# MicroController_RGB_LED.net
KiCad netlist of a schematic drawn in Altium Designer
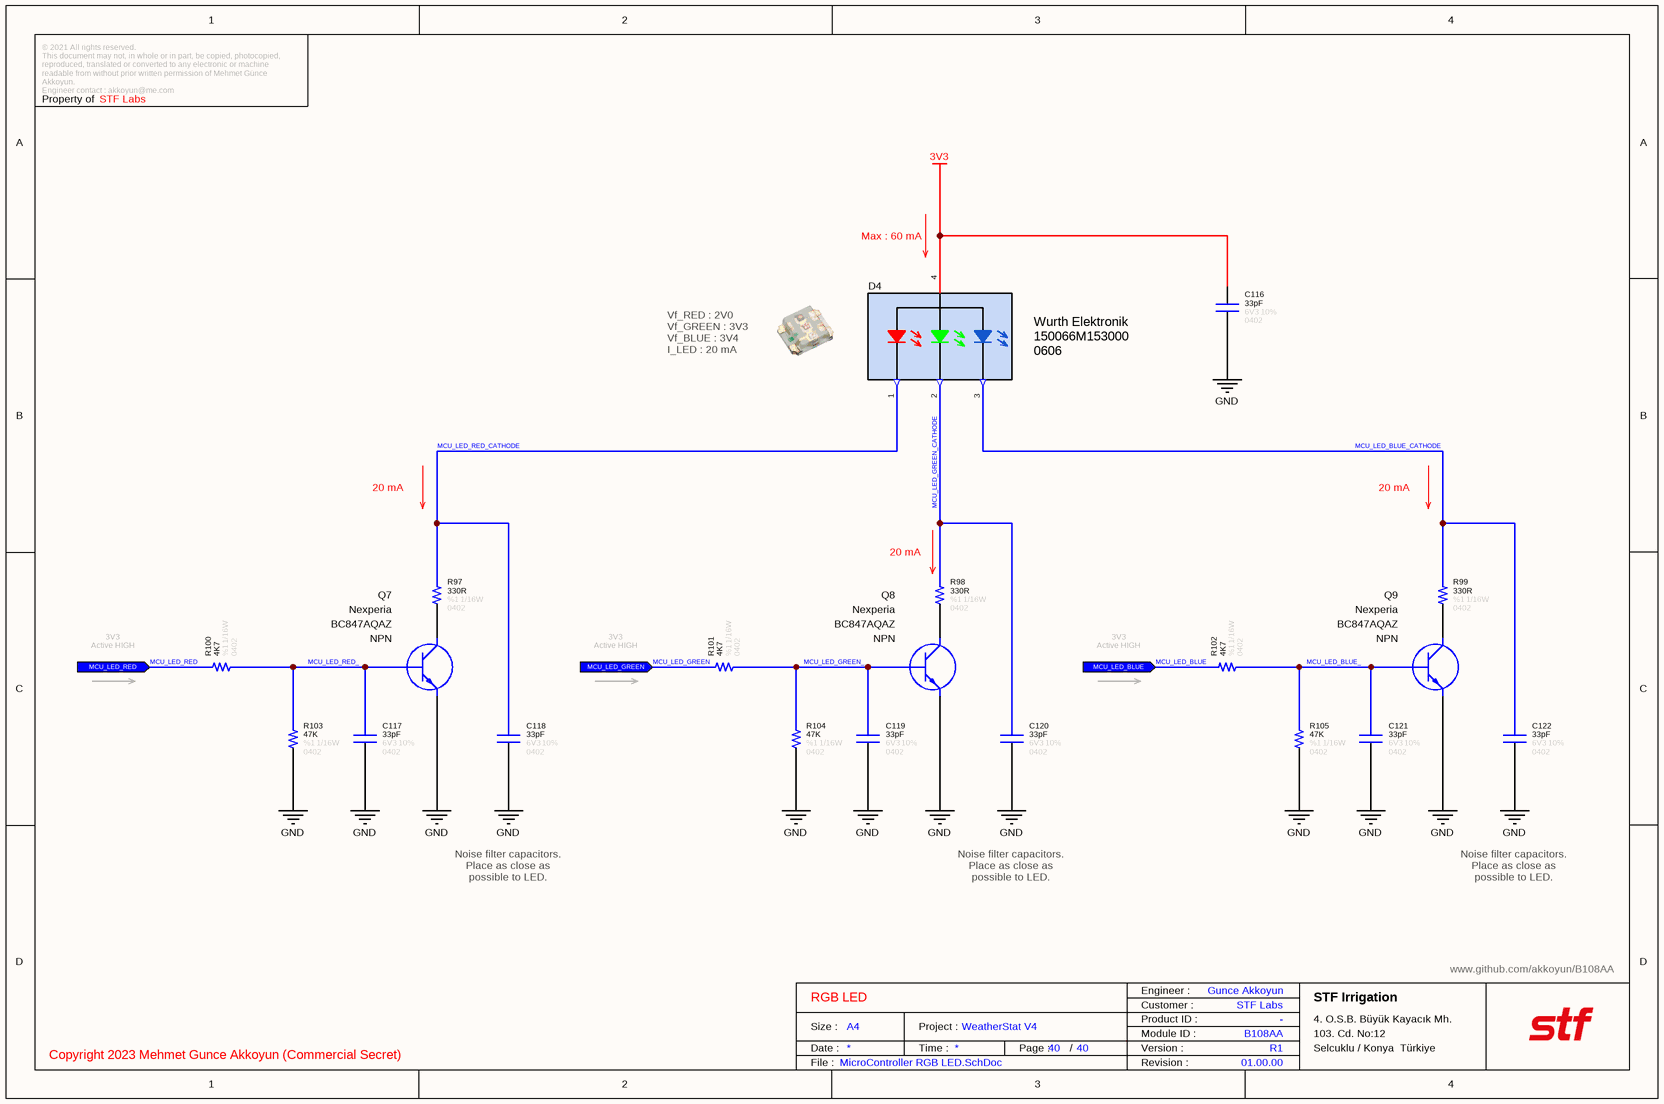
[diagram p0: MicroController RGB LED.SchDoc]

(export (version "E")
  (design (tool "Eeschema 10.0.6"))
  (components
    (comp (ref "C116")
      (value "33pF")
      (footprint "CAPACITOR_0402")
      (description "Capacitor - 33pF [0402] (Ceramic)")
      (fields
        (field (name "MANUFACTURER PART NUMBER") "C0402C330J9RACAUTO")
        (field (name "TOLERANCE") "10%")
        (field (name "CASE") "0402")
        (field (name "VOLTAGE") "6V3")
      )
      (libsource (lib "Akkoyun") (part "Capacitor - 33pF [0402-6V3]"))
    )
    (comp (ref "C117")
      (value "33pF")
      (footprint "CAPACITOR_0402")
      (description "Capacitor - 33pF [0402] (Ceramic)")
      (fields
        (field (name "MANUFACTURER PART NUMBER") "C0402C330J9RACAUTO")
        (field (name "TOLERANCE") "10%")
        (field (name "CASE") "0402")
        (field (name "VOLTAGE") "6V3")
      )
      (libsource (lib "Akkoyun") (part "Capacitor - 33pF [0402-6V3]"))
    )
    (comp (ref "C118")
      (value "33pF")
      (footprint "CAPACITOR_0402")
      (description "Capacitor - 33pF [0402] (Ceramic)")
      (fields
        (field (name "MANUFACTURER PART NUMBER") "C0402C330J9RACAUTO")
        (field (name "TOLERANCE") "10%")
        (field (name "CASE") "0402")
        (field (name "VOLTAGE") "6V3")
      )
      (libsource (lib "Akkoyun") (part "Capacitor - 33pF [0402-6V3]"))
    )
    (comp (ref "C119")
      (value "33pF")
      (footprint "CAPACITOR_0402")
      (description "Capacitor - 33pF [0402] (Ceramic)")
      (fields
        (field (name "MANUFACTURER PART NUMBER") "C0402C330J9RACAUTO")
        (field (name "TOLERANCE") "10%")
        (field (name "CASE") "0402")
        (field (name "VOLTAGE") "6V3")
      )
      (libsource (lib "Akkoyun") (part "Capacitor - 33pF [0402-6V3]"))
    )
    (comp (ref "C120")
      (value "33pF")
      (footprint "CAPACITOR_0402")
      (description "Capacitor - 33pF [0402] (Ceramic)")
      (fields
        (field (name "MANUFACTURER PART NUMBER") "C0402C330J9RACAUTO")
        (field (name "TOLERANCE") "10%")
        (field (name "CASE") "0402")
        (field (name "VOLTAGE") "6V3")
      )
      (libsource (lib "Akkoyun") (part "Capacitor - 33pF [0402-6V3]"))
    )
    (comp (ref "C121")
      (value "33pF")
      (footprint "CAPACITOR_0402")
      (description "Capacitor - 33pF [0402] (Ceramic)")
      (fields
        (field (name "MANUFACTURER PART NUMBER") "C0402C330J9RACAUTO")
        (field (name "TOLERANCE") "10%")
        (field (name "CASE") "0402")
        (field (name "VOLTAGE") "6V3")
      )
      (libsource (lib "Akkoyun") (part "Capacitor - 33pF [0402-6V3]"))
    )
    (comp (ref "C122")
      (value "33pF")
      (footprint "CAPACITOR_0402")
      (description "Capacitor - 33pF [0402] (Ceramic)")
      (fields
        (field (name "MANUFACTURER PART NUMBER") "C0402C330J9RACAUTO")
        (field (name "TOLERANCE") "10%")
        (field (name "CASE") "0402")
        (field (name "VOLTAGE") "6V3")
      )
      (libsource (lib "Akkoyun") (part "Capacitor - 33pF [0402-6V3]"))
    )
    (comp (ref "D4")
      (value "150066M153000")
      (footprint "Wurth_0606")
      (description "LED RGB DIFFUSED SMD")
      (fields
        (field (name "MANUFACTURER NAME") "Wurth Elektronik")
        (field (name "MANUFACTURER PART NUMBER") "150066M153000")
        (field (name "CASE") "0606")
      )
      (libsource (lib "Akkoyun") (part "Diode - LED-RGB"))
    )
    (comp (ref "Q7")
      (value "BC847AQAZ")
      (footprint "SOT1215")
      (description "Bipolar NPN Transistors")
      (fields
        (field (name "MANUFACTURER NAME") "Nexperia")
        (field (name "MANUFACTURER PART NUMBER") "BC847AQAZ")
        (field (name "POLARITY") "NPN")
      )
      (libsource (lib "Akkoyun") (part "Transistor - BC847"))
    )
    (comp (ref "Q8")
      (value "BC847AQAZ")
      (footprint "SOT1215")
      (description "Bipolar NPN Transistors")
      (fields
        (field (name "MANUFACTURER NAME") "Nexperia")
        (field (name "MANUFACTURER PART NUMBER") "BC847AQAZ")
        (field (name "POLARITY") "NPN")
      )
      (libsource (lib "Akkoyun") (part "Transistor - BC847"))
    )
    (comp (ref "Q9")
      (value "BC847AQAZ")
      (footprint "SOT1215")
      (description "Bipolar NPN Transistors")
      (fields
        (field (name "MANUFACTURER NAME") "Nexperia")
        (field (name "MANUFACTURER PART NUMBER") "BC847AQAZ")
        (field (name "POLARITY") "NPN")
      )
      (libsource (lib "Akkoyun") (part "Transistor - BC847"))
    )
    (comp (ref "R97")
      (value "330R")
      (footprint "RESISTOR_0402")
      (description "Thick Film Resistors - SMD 1/16 W 330 Ohm 1%")
      (fields
        (field (name "MANUFACTURER PART NUMBER") "CRCW0402330RFKED")
        (field (name "CASE") "0402")
        (field (name "TOLERANCE") "%1")
        (field (name "POWER") "1/16W")
        (field (name "Comment") "330R - 0402 - %1 - 1/16W")
      )
      (libsource (lib "Akkoyun") (part "Resistor - 330R [0402]"))
    )
    (comp (ref "R98")
      (value "330R")
      (footprint "RESISTOR_0402")
      (description "Thick Film Resistors - SMD 1/16 W 330 Ohm 1%")
      (fields
        (field (name "MANUFACTURER PART NUMBER") "CRCW0402330RFKED")
        (field (name "CASE") "0402")
        (field (name "TOLERANCE") "%1")
        (field (name "POWER") "1/16W")
        (field (name "Comment") "330R - 0402 - %1 - 1/16W")
      )
      (libsource (lib "Akkoyun") (part "Resistor - 330R [0402]"))
    )
    (comp (ref "R99")
      (value "330R")
      (footprint "RESISTOR_0402")
      (description "Thick Film Resistors - SMD 1/16 W 330 Ohm 1%")
      (fields
        (field (name "MANUFACTURER PART NUMBER") "CRCW0402330RFKED")
        (field (name "CASE") "0402")
        (field (name "TOLERANCE") "%1")
        (field (name "POWER") "1/16W")
        (field (name "Comment") "330R - 0402 - %1 - 1/16W")
      )
      (libsource (lib "Akkoyun") (part "Resistor - 330R [0402]"))
    )
    (comp (ref "R100")
      (value "4K7")
      (footprint "RESISTOR_0402")
      (description "Thick Film Resistors - SMD 1/16 W 4.7 KOhm 1%")
      (fields
        (field (name "MANUFACTURER PART NUMBER") "CRCW04024K70FKED")
        (field (name "TOLERANCE") "%1")
        (field (name "CASE") "0402")
        (field (name "POWER") "1/16W")
        (field (name "Comment") "4K7 - 0402 - %1 - 1/16W")
      )
      (libsource (lib "Akkoyun") (part "Resistor - 4K7 [0402]"))
    )
    (comp (ref "R101")
      (value "4K7")
      (footprint "RESISTOR_0402")
      (description "Thick Film Resistors - SMD 1/16 W 4.7 KOhm 1%")
      (fields
        (field (name "MANUFACTURER PART NUMBER") "CRCW04024K70FKED")
        (field (name "TOLERANCE") "%1")
        (field (name "CASE") "0402")
        (field (name "POWER") "1/16W")
        (field (name "Comment") "4K7 - 0402 - %1 - 1/16W")
      )
      (libsource (lib "Akkoyun") (part "Resistor - 4K7 [0402]"))
    )
    (comp (ref "R102")
      (value "4K7")
      (footprint "RESISTOR_0402")
      (description "Thick Film Resistors - SMD 1/16 W 4.7 KOhm 1%")
      (fields
        (field (name "MANUFACTURER PART NUMBER") "CRCW04024K70FKED")
        (field (name "TOLERANCE") "%1")
        (field (name "CASE") "0402")
        (field (name "POWER") "1/16W")
        (field (name "Comment") "4K7 - 0402 - %1 - 1/16W")
      )
      (libsource (lib "Akkoyun") (part "Resistor - 4K7 [0402]"))
    )
    (comp (ref "R103")
      (value "47K")
      (footprint "RESISTOR_0402")
      (description "Thick Film Resistors - SMD 1/16 W 47 KOhm 1%")
      (fields
        (field (name "MANUFACTURER PART NUMBER") "CRCW040247K0FKED")
        (field (name "TOLERANCE") "%1")
        (field (name "CASE") "0402")
        (field (name "POWER") "1/16W")
        (field (name "Comment") "47K - 0402 - %1 - 1/16W")
      )
      (libsource (lib "Akkoyun") (part "Resistor - 47K [0402]"))
    )
    (comp (ref "R104")
      (value "47K")
      (footprint "RESISTOR_0402")
      (description "Thick Film Resistors - SMD 1/16 W 47 KOhm 1%")
      (fields
        (field (name "MANUFACTURER PART NUMBER") "CRCW040247K0FKED")
        (field (name "TOLERANCE") "%1")
        (field (name "CASE") "0402")
        (field (name "POWER") "1/16W")
        (field (name "Comment") "47K - 0402 - %1 - 1/16W")
      )
      (libsource (lib "Akkoyun") (part "Resistor - 47K [0402]"))
    )
    (comp (ref "R105")
      (value "47K")
      (footprint "RESISTOR_0402")
      (description "Thick Film Resistors - SMD 1/16 W 47 KOhm 1%")
      (fields
        (field (name "MANUFACTURER PART NUMBER") "CRCW040247K0FKED")
        (field (name "TOLERANCE") "%1")
        (field (name "CASE") "0402")
        (field (name "POWER") "1/16W")
        (field (name "Comment") "47K - 0402 - %1 - 1/16W")
      )
      (libsource (lib "Akkoyun") (part "Resistor - 47K [0402]"))
    )
  )
  (nets
    (net (code "1") (name "/MCU_LED_BLUE") (class "Default")
      (node (ref "R102") (pin "2") (pinfunction "2_2") (pintype "passive"))
    )
    (net (code "2") (name "/MCU_LED_BLUE_") (class "Default")
      (node (ref "C121") (pin "2") (pinfunction "2_2") (pintype "passive"))
      (node (ref "Q9") (pin "1") (pinfunction "B_1") (pintype "passive"))
      (node (ref "R102") (pin "1") (pinfunction "1_1") (pintype "passive"))
      (node (ref "R105") (pin "2") (pinfunction "2_2") (pintype "passive"))
    )
    (net (code "3") (name "/MCU_LED_BLUE_CATHODE") (class "Default")
      (node (ref "C122") (pin "2") (pinfunction "2_2") (pintype "passive"))
      (node (ref "D4") (pin "3") (pinfunction "3_3") (pintype "output"))
      (node (ref "R99") (pin "2") (pinfunction "2_2") (pintype "passive"))
    )
    (net (code "4") (name "/MCU_LED_GREEN") (class "Default")
      (node (ref "R101") (pin "2") (pinfunction "2_2") (pintype "passive"))
    )
    (net (code "5") (name "/MCU_LED_GREEN_") (class "Default")
      (node (ref "C119") (pin "2") (pinfunction "2_2") (pintype "passive"))
      (node (ref "Q8") (pin "1") (pinfunction "B_1") (pintype "passive"))
      (node (ref "R101") (pin "1") (pinfunction "1_1") (pintype "passive"))
      (node (ref "R104") (pin "2") (pinfunction "2_2") (pintype "passive"))
    )
    (net (code "6") (name "/MCU_LED_GREEN_CATHODE") (class "Default")
      (node (ref "C120") (pin "2") (pinfunction "2_2") (pintype "passive"))
      (node (ref "D4") (pin "2") (pinfunction "2_2") (pintype "output"))
      (node (ref "R98") (pin "2") (pinfunction "2_2") (pintype "passive"))
    )
    (net (code "7") (name "/MCU_LED_RED") (class "Default")
      (node (ref "R100") (pin "2") (pinfunction "2_2") (pintype "passive"))
    )
    (net (code "8") (name "/MCU_LED_RED_") (class "Default")
      (node (ref "C117") (pin "2") (pinfunction "2_2") (pintype "passive"))
      (node (ref "Q7") (pin "1") (pinfunction "B_1") (pintype "passive"))
      (node (ref "R100") (pin "1") (pinfunction "1_1") (pintype "passive"))
      (node (ref "R103") (pin "2") (pinfunction "2_2") (pintype "passive"))
    )
    (net (code "9") (name "/MCU_LED_RED_CATHODE") (class "Default")
      (node (ref "C118") (pin "2") (pinfunction "2_2") (pintype "passive"))
      (node (ref "D4") (pin "1") (pinfunction "1_1") (pintype "output"))
      (node (ref "R97") (pin "2") (pinfunction "2_2") (pintype "passive"))
    )
    (net (code "10") (name "3V3") (class "Default")
      (node (ref "C116") (pin "2") (pinfunction "2_2") (pintype "passive"))
      (node (ref "D4") (pin "4") (pinfunction "4_4") (pintype "power_in"))
    )
    (net (code "11") (name "GND") (class "Default")
      (node (ref "C116") (pin "1") (pinfunction "1_1") (pintype "passive"))
      (node (ref "C117") (pin "1") (pinfunction "1_1") (pintype "passive"))
      (node (ref "C118") (pin "1") (pinfunction "1_1") (pintype "passive"))
      (node (ref "C119") (pin "1") (pinfunction "1_1") (pintype "passive"))
      (node (ref "C120") (pin "1") (pinfunction "1_1") (pintype "passive"))
      (node (ref "C121") (pin "1") (pinfunction "1_1") (pintype "passive"))
      (node (ref "C122") (pin "1") (pinfunction "1_1") (pintype "passive"))
      (node (ref "Q7") (pin "2") (pinfunction "E_2") (pintype "passive"))
      (node (ref "Q8") (pin "2") (pinfunction "E_2") (pintype "passive"))
      (node (ref "Q9") (pin "2") (pinfunction "E_2") (pintype "passive"))
      (node (ref "R103") (pin "1") (pinfunction "1_1") (pintype "passive"))
      (node (ref "R104") (pin "1") (pinfunction "1_1") (pintype "passive"))
      (node (ref "R105") (pin "1") (pinfunction "1_1") (pintype "passive"))
    )
    (net (code "12") (name "Net-(Q7-C)") (class "Default")
      (node (ref "Q7") (pin "3") (pinfunction "C_3") (pintype "passive"))
      (node (ref "R97") (pin "1") (pinfunction "1_1") (pintype "passive"))
    )
    (net (code "13") (name "Net-(Q8-C)") (class "Default")
      (node (ref "Q8") (pin "3") (pinfunction "C_3") (pintype "passive"))
      (node (ref "R98") (pin "1") (pinfunction "1_1") (pintype "passive"))
    )
    (net (code "14") (name "Net-(Q9-C)") (class "Default")
      (node (ref "Q9") (pin "3") (pinfunction "C_3") (pintype "passive"))
      (node (ref "R99") (pin "1") (pinfunction "1_1") (pintype "passive"))
    )
  )
)
